# killswitch.net
KiCad netlist of a schematic drawn in Altium Designer
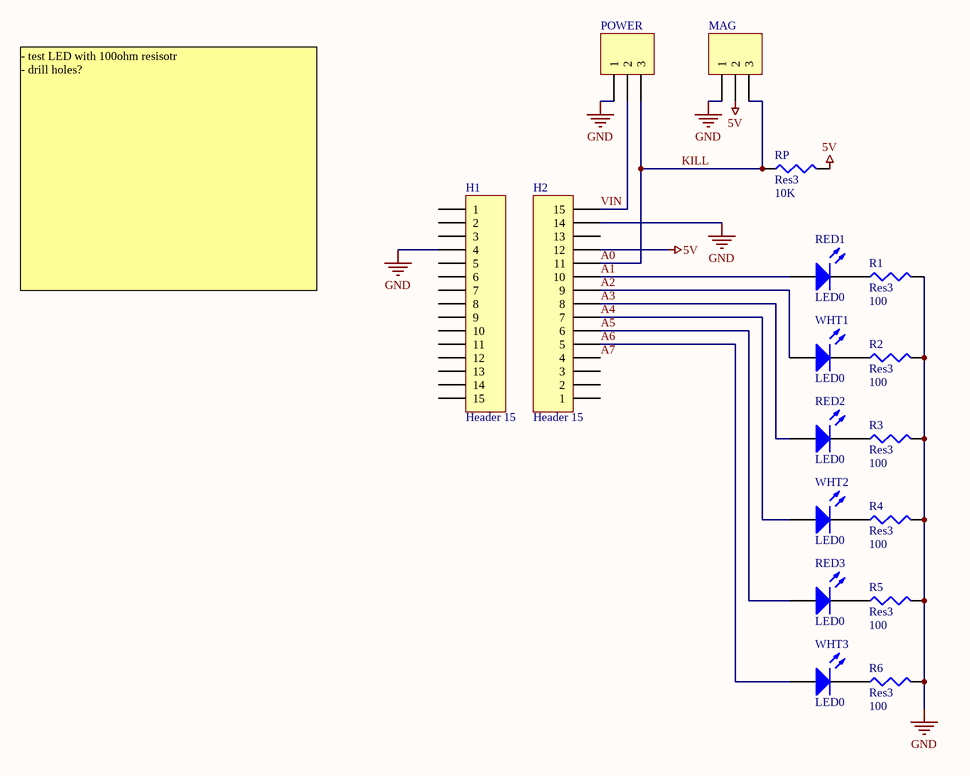
[diagram p0: killswitch.SchDoc]

(export (version "E")
  (design (tool "Eeschema 10.0.6"))
  (components
    (comp (ref "H1")
      (value "Header 15")
      (footprint "HDR1X15")
      (description "Header, 15-Pin")
      (fields (field (name "PUBLISHER") "Altium Limited"))
      (libsource (lib "Miscellaneous Connectors") (part "Header 15"))
    )
    (comp (ref "H2")
      (value "Header 15")
      (footprint "HDR1X15")
      (description "Header, 15-Pin")
      (fields (field (name "PUBLISHER") "Altium Limited"))
      (libsource (lib "") (part "Header 15_1"))
    )
    (comp (ref "MAG")
      (value "Header 3")
      (footprint "HDR1X3")
      (description "Header, 3-Pin")
      (fields (field (name "PUBLISHER") "Altium Limited"))
      (libsource (lib "Miscellaneous Connectors") (part "Header 3"))
    )
    (comp (ref "POWER")
      (value "Header 3")
      (footprint "HDR1X3")
      (description "Header, 3-Pin")
      (fields (field (name "PUBLISHER") "Altium Limited"))
      (libsource (lib "Miscellaneous Connectors") (part "Header 3"))
    )
    (comp (ref "R1")
      (value "Res3")
      (footprint "0805_RES")
      (description "Resistor")
      (fields (field (name "ALTIUM_VALUE") "100") (field (name "PUBLISHER") "Altium Limited"))
      (libsource (lib "Miscellaneous Devices") (part "Res3"))
    )
    (comp (ref "R2")
      (value "Res3")
      (footprint "0805_RES")
      (description "Resistor")
      (fields (field (name "ALTIUM_VALUE") "100") (field (name "PUBLISHER") "Altium Limited"))
      (libsource (lib "Miscellaneous Devices") (part "Res3"))
    )
    (comp (ref "R3")
      (value "Res3")
      (footprint "0805_RES")
      (description "Resistor")
      (fields (field (name "ALTIUM_VALUE") "100") (field (name "PUBLISHER") "Altium Limited"))
      (libsource (lib "Miscellaneous Devices") (part "Res3"))
    )
    (comp (ref "R4")
      (value "Res3")
      (footprint "0805_RES")
      (description "Resistor")
      (fields (field (name "ALTIUM_VALUE") "100") (field (name "PUBLISHER") "Altium Limited"))
      (libsource (lib "Miscellaneous Devices") (part "Res3"))
    )
    (comp (ref "R5")
      (value "Res3")
      (footprint "0805_RES")
      (description "Resistor")
      (fields (field (name "ALTIUM_VALUE") "100") (field (name "PUBLISHER") "Altium Limited"))
      (libsource (lib "Miscellaneous Devices") (part "Res3"))
    )
    (comp (ref "R6")
      (value "Res3")
      (footprint "0805_RES")
      (description "Resistor")
      (fields (field (name "ALTIUM_VALUE") "100") (field (name "PUBLISHER") "Altium Limited"))
      (libsource (lib "Miscellaneous Devices") (part "Res3"))
    )
    (comp (ref "RED1")
      (value "LED0")
      (footprint "cree_led")
      (description "Typical INFRARED GaAs LED")
      (fields (field (name "PUBLISHER") "Altium Limited"))
      (libsource (lib "Miscellaneous Devices") (part "LED0"))
    )
    (comp (ref "RED2")
      (value "LED0")
      (footprint "cree_led")
      (description "Typical INFRARED GaAs LED")
      (fields (field (name "PUBLISHER") "Altium Limited"))
      (libsource (lib "Miscellaneous Devices") (part "LED0"))
    )
    (comp (ref "RED3")
      (value "LED0")
      (footprint "cree_led")
      (description "Typical INFRARED GaAs LED")
      (fields (field (name "PUBLISHER") "Altium Limited"))
      (libsource (lib "Miscellaneous Devices") (part "LED0"))
    )
    (comp (ref "RP")
      (value "Res3")
      (footprint "0805_RES")
      (description "Resistor")
      (fields (field (name "ALTIUM_VALUE") "10K") (field (name "PUBLISHER") "Altium Limited"))
      (libsource (lib "Miscellaneous Devices") (part "Res3"))
    )
    (comp (ref "WHT1")
      (value "LED0")
      (footprint "cree_led")
      (description "Typical INFRARED GaAs LED")
      (fields (field (name "PUBLISHER") "Altium Limited"))
      (libsource (lib "Miscellaneous Devices") (part "LED0"))
    )
    (comp (ref "WHT2")
      (value "LED0")
      (footprint "cree_led")
      (description "Typical INFRARED GaAs LED")
      (fields (field (name "PUBLISHER") "Altium Limited"))
      (libsource (lib "Miscellaneous Devices") (part "LED0"))
    )
    (comp (ref "WHT3")
      (value "LED0")
      (footprint "cree_led")
      (description "Typical INFRARED GaAs LED")
      (fields (field (name "PUBLISHER") "Altium Limited"))
      (libsource (lib "Miscellaneous Devices") (part "LED0"))
    )
  )
  (nets
    (net (code "1") (name "/A0") (class "Default")
      (node (ref "H2") (pin "11") (pinfunction "11_11") (pintype "passive"))
      (node (ref "MAG") (pin "3") (pinfunction "3_3") (pintype "passive"))
      (node (ref "POWER") (pin "3") (pinfunction "3_3") (pintype "passive"))
      (node (ref "RP") (pin "1") (pinfunction "1_1") (pintype "passive"))
    )
    (net (code "2") (name "/A1") (class "Default")
      (node (ref "H2") (pin "10") (pinfunction "10_10") (pintype "passive"))
      (node (ref "RED1") (pin "1") (pinfunction "A_1") (pintype "passive"))
    )
    (net (code "3") (name "/A2") (class "Default")
      (node (ref "H2") (pin "9") (pinfunction "9_9") (pintype "passive"))
      (node (ref "WHT1") (pin "1") (pinfunction "A_1") (pintype "passive"))
    )
    (net (code "4") (name "/A3") (class "Default")
      (node (ref "H2") (pin "8") (pinfunction "8_8") (pintype "passive"))
      (node (ref "RED2") (pin "1") (pinfunction "A_1") (pintype "passive"))
    )
    (net (code "5") (name "/A4") (class "Default")
      (node (ref "H2") (pin "7") (pinfunction "7_7") (pintype "passive"))
      (node (ref "WHT2") (pin "1") (pinfunction "A_1") (pintype "passive"))
    )
    (net (code "6") (name "/A5") (class "Default")
      (node (ref "H2") (pin "6") (pinfunction "6_6") (pintype "passive"))
      (node (ref "RED3") (pin "1") (pinfunction "A_1") (pintype "passive"))
    )
    (net (code "7") (name "/A6") (class "Default")
      (node (ref "H2") (pin "5") (pinfunction "5_5") (pintype "passive"))
      (node (ref "WHT3") (pin "1") (pinfunction "A_1") (pintype "passive"))
    )
    (net (code "8") (name "/A7") (class "Default")
      (node (ref "H2") (pin "4") (pinfunction "4_4") (pintype "passive"))
    )
    (net (code "9") (name "/VIN") (class "Default")
      (node (ref "H2") (pin "15") (pinfunction "15_15") (pintype "passive"))
      (node (ref "POWER") (pin "2") (pinfunction "2_2") (pintype "passive"))
    )
    (net (code "10") (name "5V") (class "Default")
      (node (ref "H2") (pin "12") (pinfunction "12_12") (pintype "passive"))
      (node (ref "MAG") (pin "2") (pinfunction "2_2") (pintype "passive"))
      (node (ref "RP") (pin "2") (pinfunction "2_2") (pintype "passive"))
    )
    (net (code "11") (name "GND") (class "Default")
      (node (ref "H1") (pin "4") (pinfunction "4_4") (pintype "passive"))
      (node (ref "H2") (pin "14") (pinfunction "14_14") (pintype "passive"))
      (node (ref "MAG") (pin "1") (pinfunction "1_1") (pintype "passive"))
      (node (ref "POWER") (pin "1") (pinfunction "1_1") (pintype "passive"))
      (node (ref "R1") (pin "2") (pinfunction "2_2") (pintype "passive"))
      (node (ref "R2") (pin "2") (pinfunction "2_2") (pintype "passive"))
      (node (ref "R3") (pin "2") (pinfunction "2_2") (pintype "passive"))
      (node (ref "R4") (pin "2") (pinfunction "2_2") (pintype "passive"))
      (node (ref "R5") (pin "2") (pinfunction "2_2") (pintype "passive"))
      (node (ref "R6") (pin "2") (pinfunction "2_2") (pintype "passive"))
    )
    (net (code "12") (name "Net-(RED1-K)") (class "Default")
      (node (ref "R1") (pin "1") (pinfunction "1_1") (pintype "passive"))
      (node (ref "RED1") (pin "2") (pinfunction "K_2") (pintype "passive"))
    )
    (net (code "13") (name "Net-(RED2-K)") (class "Default")
      (node (ref "R3") (pin "1") (pinfunction "1_1") (pintype "passive"))
      (node (ref "RED2") (pin "2") (pinfunction "K_2") (pintype "passive"))
    )
    (net (code "14") (name "Net-(RED3-K)") (class "Default")
      (node (ref "R5") (pin "1") (pinfunction "1_1") (pintype "passive"))
      (node (ref "RED3") (pin "2") (pinfunction "K_2") (pintype "passive"))
    )
    (net (code "15") (name "Net-(WHT1-K)") (class "Default")
      (node (ref "R2") (pin "1") (pinfunction "1_1") (pintype "passive"))
      (node (ref "WHT1") (pin "2") (pinfunction "K_2") (pintype "passive"))
    )
    (net (code "16") (name "Net-(WHT2-K)") (class "Default")
      (node (ref "R4") (pin "1") (pinfunction "1_1") (pintype "passive"))
      (node (ref "WHT2") (pin "2") (pinfunction "K_2") (pintype "passive"))
    )
    (net (code "17") (name "Net-(WHT3-K)") (class "Default")
      (node (ref "R6") (pin "1") (pinfunction "1_1") (pintype "passive"))
      (node (ref "WHT3") (pin "2") (pinfunction "K_2") (pintype "passive"))
    )
    (net (code "18") (name "unconnected-(H1-Pad1)") (class "Default")
      (node (ref "H1") (pin "1") (pinfunction "1_1") (pintype "passive"))
    )
    (net (code "19") (name "unconnected-(H1-Pad2)") (class "Default")
      (node (ref "H1") (pin "2") (pinfunction "2_2") (pintype "passive"))
    )
    (net (code "20") (name "unconnected-(H1-Pad3)") (class "Default")
      (node (ref "H1") (pin "3") (pinfunction "3_3") (pintype "passive"))
    )
    (net (code "21") (name "unconnected-(H1-Pad5)") (class "Default")
      (node (ref "H1") (pin "5") (pinfunction "5_5") (pintype "passive"))
    )
    (net (code "22") (name "unconnected-(H1-Pad6)") (class "Default")
      (node (ref "H1") (pin "6") (pinfunction "6_6") (pintype "passive"))
    )
    (net (code "23") (name "unconnected-(H1-Pad7)") (class "Default")
      (node (ref "H1") (pin "7") (pinfunction "7_7") (pintype "passive"))
    )
    (net (code "24") (name "unconnected-(H1-Pad8)") (class "Default")
      (node (ref "H1") (pin "8") (pinfunction "8_8") (pintype "passive"))
    )
    (net (code "25") (name "unconnected-(H1-Pad9)") (class "Default")
      (node (ref "H1") (pin "9") (pinfunction "9_9") (pintype "passive"))
    )
    (net (code "26") (name "unconnected-(H1-Pad10)") (class "Default")
      (node (ref "H1") (pin "10") (pinfunction "10_10") (pintype "passive"))
    )
    (net (code "27") (name "unconnected-(H1-Pad11)") (class "Default")
      (node (ref "H1") (pin "11") (pinfunction "11_11") (pintype "passive"))
    )
    (net (code "28") (name "unconnected-(H1-Pad12)") (class "Default")
      (node (ref "H1") (pin "12") (pinfunction "12_12") (pintype "passive"))
    )
    (net (code "29") (name "unconnected-(H1-Pad13)") (class "Default")
      (node (ref "H1") (pin "13") (pinfunction "13_13") (pintype "passive"))
    )
    (net (code "30") (name "unconnected-(H1-Pad14)") (class "Default")
      (node (ref "H1") (pin "14") (pinfunction "14_14") (pintype "passive"))
    )
    (net (code "31") (name "unconnected-(H1-Pad15)") (class "Default")
      (node (ref "H1") (pin "15") (pinfunction "15_15") (pintype "passive"))
    )
    (net (code "32") (name "unconnected-(H2-Pad1)") (class "Default")
      (node (ref "H2") (pin "1") (pinfunction "1_1") (pintype "passive"))
    )
    (net (code "33") (name "unconnected-(H2-Pad2)") (class "Default")
      (node (ref "H2") (pin "2") (pinfunction "2_2") (pintype "passive"))
    )
    (net (code "34") (name "unconnected-(H2-Pad3)") (class "Default")
      (node (ref "H2") (pin "3") (pinfunction "3_3") (pintype "passive"))
    )
    (net (code "35") (name "unconnected-(H2-Pad13)") (class "Default")
      (node (ref "H2") (pin "13") (pinfunction "13_13") (pintype "passive"))
    )
  )
)
